# sensor.net
KiCad netlist of a schematic drawn in EAGLE
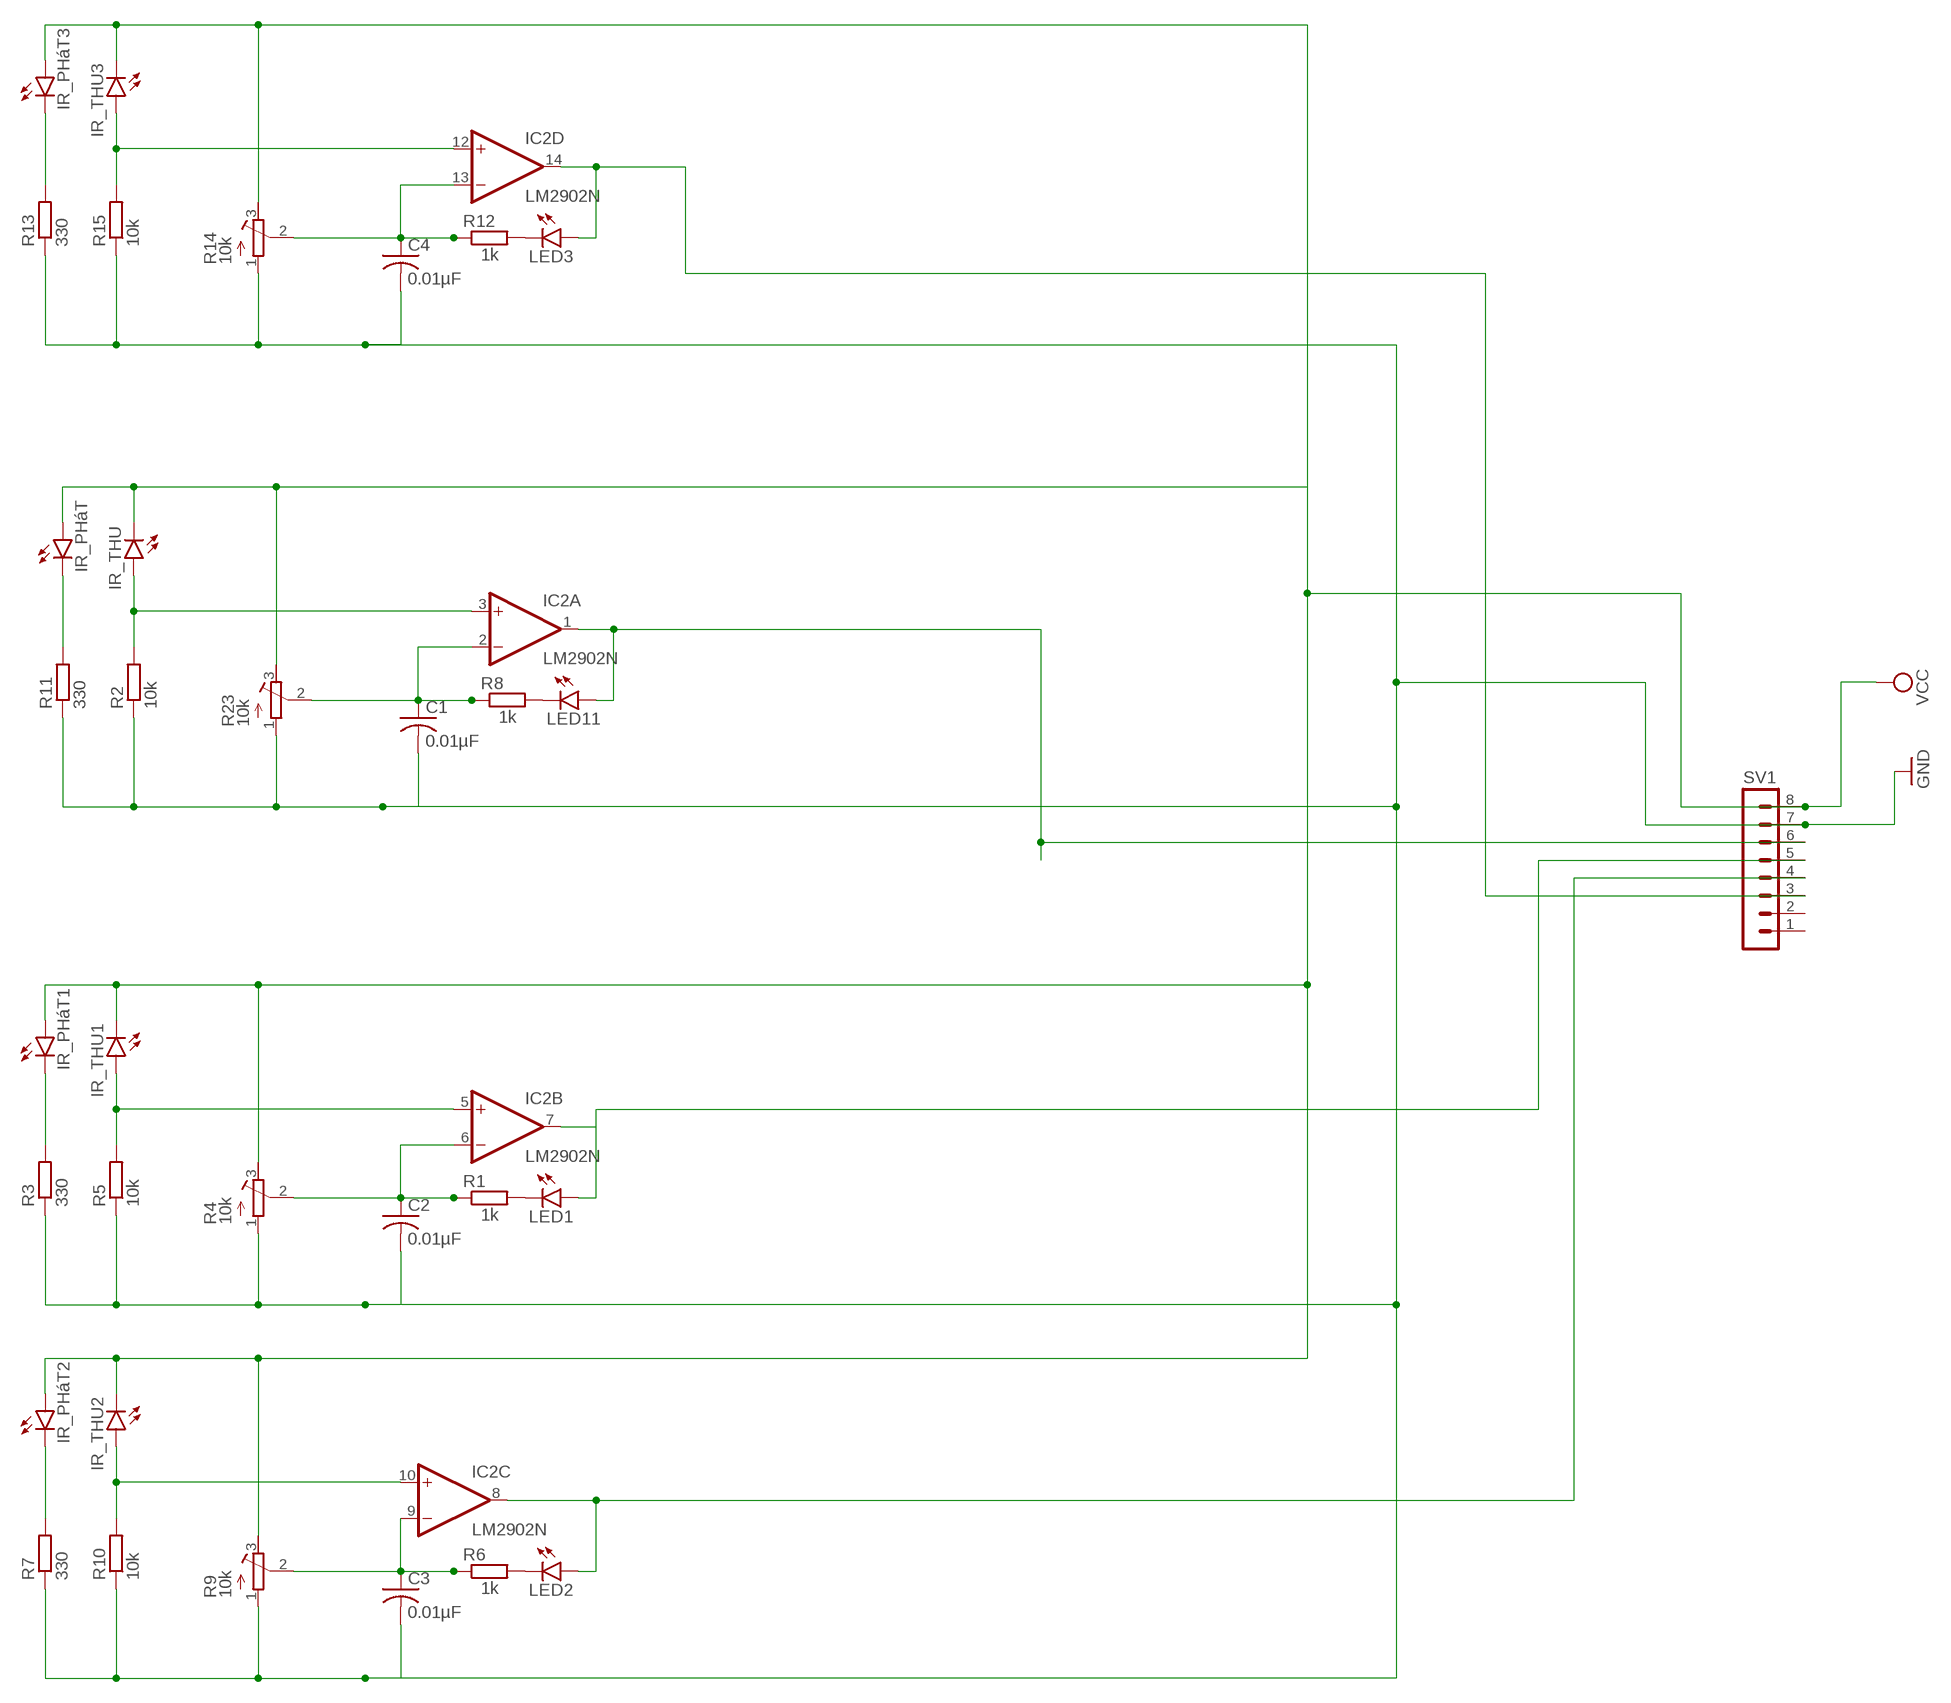
[diagram p0: schematic, sheet 1]

(export (version "E")
  (design (tool "Eeschema 10.0.6"))
  (components
    (comp (ref "C1")
      (value "0.01µF")
      (footprint "eagle-import:C025-040X050")
      (libsource (lib "eagle-import") (part "C-US025-040X050"))
    )
    (comp (ref "C2")
      (value "0.01µF")
      (footprint "eagle-import:C025-040X050")
      (libsource (lib "eagle-import") (part "C-US025-040X050"))
    )
    (comp (ref "C3")
      (value "0.01µF")
      (footprint "eagle-import:C025-040X050")
      (libsource (lib "eagle-import") (part "C-US025-040X050"))
    )
    (comp (ref "C4")
      (value "0.01µF")
      (footprint "eagle-import:C025-040X050")
      (libsource (lib "eagle-import") (part "C-US025-040X050"))
    )
    (comp (ref "IC2")
      (value "LM2902N")
      (footprint "eagle-import:DIL14")
      (fields (field (name "SPICEPREFIX") "J"))
      (libsource (lib "eagle-import") (part "LM2902N"))
    )
    (comp (ref "IR_PHáT")
      (value "LED5MM")
      (footprint "eagle-import:LED5MM")
      (libsource (lib "eagle-import") (part "LED5MM"))
    )
    (comp (ref "IR_PHáT1")
      (value "LED5MM")
      (footprint "eagle-import:LED5MM")
      (libsource (lib "eagle-import") (part "LED5MM"))
    )
    (comp (ref "IR_PHáT2")
      (value "LED5MM")
      (footprint "eagle-import:LED5MM")
      (libsource (lib "eagle-import") (part "LED5MM"))
    )
    (comp (ref "IR_PHáT3")
      (value "LED5MM")
      (footprint "eagle-import:LED5MM")
      (libsource (lib "eagle-import") (part "LED5MM"))
    )
    (comp (ref "IR_THU")
      (value "LED5MM")
      (footprint "eagle-import:LED5MM")
      (libsource (lib "eagle-import") (part "LED5MM"))
    )
    (comp (ref "IR_THU1")
      (value "LED5MM")
      (footprint "eagle-import:LED5MM")
      (libsource (lib "eagle-import") (part "LED5MM"))
    )
    (comp (ref "IR_THU2")
      (value "LED5MM")
      (footprint "eagle-import:LED5MM")
      (libsource (lib "eagle-import") (part "LED5MM"))
    )
    (comp (ref "IR_THU3")
      (value "LED5MM")
      (footprint "eagle-import:LED5MM")
      (libsource (lib "eagle-import") (part "LED5MM"))
    )
    (comp (ref "LED1")
      (value "LED5MM")
      (footprint "eagle-import:LED5MM")
      (libsource (lib "eagle-import") (part "LED5MM"))
    )
    (comp (ref "LED2")
      (value "LED5MM")
      (footprint "eagle-import:LED5MM")
      (libsource (lib "eagle-import") (part "LED5MM"))
    )
    (comp (ref "LED3")
      (value "LED5MM")
      (footprint "eagle-import:LED5MM")
      (libsource (lib "eagle-import") (part "LED5MM"))
    )
    (comp (ref "LED11")
      (value "LED5MM")
      (footprint "eagle-import:LED5MM")
      (libsource (lib "eagle-import") (part "LED5MM"))
    )
    (comp (ref "R1")
      (value "1k")
      (footprint "eagle-import:0204_7")
      (libsource (lib "eagle-import") (part "R-EU_0204/7"))
    )
    (comp (ref "R2")
      (value "10k")
      (footprint "eagle-import:0204_7")
      (libsource (lib "eagle-import") (part "R-EU_0204/7"))
    )
    (comp (ref "R3")
      (value "330")
      (footprint "eagle-import:0204_7")
      (libsource (lib "eagle-import") (part "R-EU_0204/7"))
    )
    (comp (ref "R4")
      (value "10k")
      (footprint "eagle-import:RTRIM3103")
      (libsource (lib "eagle-import") (part "R-TRIMM3103"))
    )
    (comp (ref "R5")
      (value "10k")
      (footprint "eagle-import:0204_7")
      (libsource (lib "eagle-import") (part "R-EU_0204/7"))
    )
    (comp (ref "R6")
      (value "1k")
      (footprint "eagle-import:0204_7")
      (libsource (lib "eagle-import") (part "R-EU_0204/7"))
    )
    (comp (ref "R7")
      (value "330")
      (footprint "eagle-import:0204_7")
      (libsource (lib "eagle-import") (part "R-EU_0204/7"))
    )
    (comp (ref "R8")
      (value "1k")
      (footprint "eagle-import:0204_7")
      (libsource (lib "eagle-import") (part "R-EU_0204/7"))
    )
    (comp (ref "R9")
      (value "10k")
      (footprint "eagle-import:RTRIM3103")
      (libsource (lib "eagle-import") (part "R-TRIMM3103"))
    )
    (comp (ref "R10")
      (value "10k")
      (footprint "eagle-import:0204_7")
      (libsource (lib "eagle-import") (part "R-EU_0204/7"))
    )
    (comp (ref "R11")
      (value "330")
      (footprint "eagle-import:0204_7")
      (libsource (lib "eagle-import") (part "R-EU_0204/7"))
    )
    (comp (ref "R12")
      (value "1k")
      (footprint "eagle-import:0204_7")
      (libsource (lib "eagle-import") (part "R-EU_0204/7"))
    )
    (comp (ref "R13")
      (value "330")
      (footprint "eagle-import:0204_7")
      (libsource (lib "eagle-import") (part "R-EU_0204/7"))
    )
    (comp (ref "R14")
      (value "10k")
      (footprint "eagle-import:RTRIM3103")
      (libsource (lib "eagle-import") (part "R-TRIMM3103"))
    )
    (comp (ref "R15")
      (value "10k")
      (footprint "eagle-import:0204_7")
      (libsource (lib "eagle-import") (part "R-EU_0204/7"))
    )
    (comp (ref "R23")
      (value "10k")
      (footprint "eagle-import:RTRIM3103")
      (libsource (lib "eagle-import") (part "R-TRIMM3103"))
    )
    (comp (ref "SV1")
      (value "MA08-1W")
      (footprint "eagle-import:MA08-1W")
      (libsource (lib "eagle-import") (part "MA08-1W"))
    )
  )
  (nets
    (net (code "1") (name "GND") (class "Default")
      (node (ref "C1") (pin "2") (pinfunction "2_2") (pintype "passive"))
      (node (ref "C2") (pin "2") (pinfunction "2_2") (pintype "passive"))
      (node (ref "C3") (pin "2") (pinfunction "2_2") (pintype "passive"))
      (node (ref "C4") (pin "2") (pinfunction "2_2") (pintype "passive"))
      (node (ref "R10") (pin "1") (pinfunction "1_1") (pintype "passive"))
      (node (ref "R11") (pin "1") (pinfunction "1_1") (pintype "passive"))
      (node (ref "R13") (pin "1") (pinfunction "1_1") (pintype "passive"))
      (node (ref "R14") (pin "1") (pinfunction "A_1") (pintype "passive"))
      (node (ref "R15") (pin "1") (pinfunction "1_1") (pintype "passive"))
      (node (ref "R2") (pin "1") (pinfunction "1_1") (pintype "passive"))
      (node (ref "R23") (pin "1") (pinfunction "A_1") (pintype "passive"))
      (node (ref "R3") (pin "1") (pinfunction "1_1") (pintype "passive"))
      (node (ref "R4") (pin "1") (pinfunction "A_1") (pintype "passive"))
      (node (ref "R5") (pin "1") (pinfunction "1_1") (pintype "passive"))
      (node (ref "R7") (pin "1") (pinfunction "1_1") (pintype "passive"))
      (node (ref "R9") (pin "1") (pinfunction "A_1") (pintype "passive"))
      (node (ref "SV1") (pin "7") (pinfunction "7_7") (pintype "passive"))
    )
    (net (code "2") (name "Net-(IC2A-+IN)") (class "Default")
      (node (ref "IC2") (pin "3") (pinfunction "+IN_3") (pintype "input"))
      (node (ref "IR_THU") (pin "A") (pinfunction "A_A") (pintype "passive"))
      (node (ref "R2") (pin "2") (pinfunction "2_2") (pintype "passive"))
    )
    (net (code "3") (name "Net-(IC2A--IN)") (class "Default")
      (node (ref "C1") (pin "1") (pinfunction "1_1") (pintype "passive"))
      (node (ref "IC2") (pin "2") (pinfunction "-IN_2") (pintype "input"))
      (node (ref "R23") (pin "2") (pinfunction "S_2") (pintype "passive"))
      (node (ref "R8") (pin "1") (pinfunction "1_1") (pintype "passive"))
    )
    (net (code "4") (name "Net-(IC2A-OUT)") (class "Default")
      (node (ref "IC2") (pin "1") (pinfunction "OUT_1") (pintype "output"))
      (node (ref "LED11") (pin "A") (pinfunction "A_A") (pintype "passive"))
      (node (ref "SV1") (pin "6") (pinfunction "6_6") (pintype "passive"))
    )
    (net (code "5") (name "Net-(IC2B-+IN)") (class "Default")
      (node (ref "IC2") (pin "5") (pinfunction "+IN_5") (pintype "input"))
      (node (ref "IR_THU1") (pin "A") (pinfunction "A_A") (pintype "passive"))
      (node (ref "R5") (pin "2") (pinfunction "2_2") (pintype "passive"))
    )
    (net (code "6") (name "Net-(IC2B--IN)") (class "Default")
      (node (ref "C2") (pin "1") (pinfunction "1_1") (pintype "passive"))
      (node (ref "IC2") (pin "6") (pinfunction "-IN_6") (pintype "input"))
      (node (ref "R1") (pin "1") (pinfunction "1_1") (pintype "passive"))
      (node (ref "R4") (pin "2") (pinfunction "S_2") (pintype "passive"))
    )
    (net (code "7") (name "Net-(IC2B-OUT)") (class "Default")
      (node (ref "IC2") (pin "7") (pinfunction "OUT_7") (pintype "output"))
      (node (ref "LED1") (pin "A") (pinfunction "A_A") (pintype "passive"))
      (node (ref "SV1") (pin "5") (pinfunction "5_5") (pintype "passive"))
    )
    (net (code "8") (name "Net-(IC2C-+IN)") (class "Default")
      (node (ref "IC2") (pin "10") (pinfunction "+IN_10") (pintype "input"))
      (node (ref "IR_THU2") (pin "A") (pinfunction "A_A") (pintype "passive"))
      (node (ref "R10") (pin "2") (pinfunction "2_2") (pintype "passive"))
    )
    (net (code "9") (name "Net-(IC2C--IN)") (class "Default")
      (node (ref "C3") (pin "1") (pinfunction "1_1") (pintype "passive"))
      (node (ref "IC2") (pin "9") (pinfunction "-IN_9") (pintype "input"))
      (node (ref "R6") (pin "1") (pinfunction "1_1") (pintype "passive"))
      (node (ref "R9") (pin "2") (pinfunction "S_2") (pintype "passive"))
    )
    (net (code "10") (name "Net-(IC2C-OUT)") (class "Default")
      (node (ref "IC2") (pin "8") (pinfunction "OUT_8") (pintype "output"))
      (node (ref "LED2") (pin "A") (pinfunction "A_A") (pintype "passive"))
      (node (ref "SV1") (pin "4") (pinfunction "4_4") (pintype "passive"))
    )
    (net (code "11") (name "Net-(IC2D-+IN)") (class "Default")
      (node (ref "IC2") (pin "12") (pinfunction "+IN_12") (pintype "input"))
      (node (ref "IR_THU3") (pin "A") (pinfunction "A_A") (pintype "passive"))
      (node (ref "R15") (pin "2") (pinfunction "2_2") (pintype "passive"))
    )
    (net (code "12") (name "Net-(IC2D--IN)") (class "Default")
      (node (ref "C4") (pin "1") (pinfunction "1_1") (pintype "passive"))
      (node (ref "IC2") (pin "13") (pinfunction "-IN_13") (pintype "input"))
      (node (ref "R12") (pin "1") (pinfunction "1_1") (pintype "passive"))
      (node (ref "R14") (pin "2") (pinfunction "S_2") (pintype "passive"))
    )
    (net (code "13") (name "Net-(IC2D-OUT)") (class "Default")
      (node (ref "IC2") (pin "14") (pinfunction "OUT_14") (pintype "output"))
      (node (ref "LED3") (pin "A") (pinfunction "A_A") (pintype "passive"))
      (node (ref "SV1") (pin "3") (pinfunction "3_3") (pintype "passive"))
    )
    (net (code "14") (name "Net-(IR_PHáT-C)") (class "Default")
      (node (ref "IR_PHáT") (pin "K") (pinfunction "C_K") (pintype "passive"))
      (node (ref "R11") (pin "2") (pinfunction "2_2") (pintype "passive"))
    )
    (net (code "15") (name "Net-(IR_PHáT1-C)") (class "Default")
      (node (ref "IR_PHáT1") (pin "K") (pinfunction "C_K") (pintype "passive"))
      (node (ref "R3") (pin "2") (pinfunction "2_2") (pintype "passive"))
    )
    (net (code "16") (name "Net-(IR_PHáT2-C)") (class "Default")
      (node (ref "IR_PHáT2") (pin "K") (pinfunction "C_K") (pintype "passive"))
      (node (ref "R7") (pin "2") (pinfunction "2_2") (pintype "passive"))
    )
    (net (code "17") (name "Net-(IR_PHáT3-C)") (class "Default")
      (node (ref "IR_PHáT3") (pin "K") (pinfunction "C_K") (pintype "passive"))
      (node (ref "R13") (pin "2") (pinfunction "2_2") (pintype "passive"))
    )
    (net (code "18") (name "Net-(LED1-C)") (class "Default")
      (node (ref "LED1") (pin "K") (pinfunction "C_K") (pintype "passive"))
      (node (ref "R1") (pin "2") (pinfunction "2_2") (pintype "passive"))
    )
    (net (code "19") (name "Net-(LED2-C)") (class "Default")
      (node (ref "LED2") (pin "K") (pinfunction "C_K") (pintype "passive"))
      (node (ref "R6") (pin "2") (pinfunction "2_2") (pintype "passive"))
    )
    (net (code "20") (name "Net-(LED3-C)") (class "Default")
      (node (ref "LED3") (pin "K") (pinfunction "C_K") (pintype "passive"))
      (node (ref "R12") (pin "2") (pinfunction "2_2") (pintype "passive"))
    )
    (net (code "21") (name "Net-(LED11-C)") (class "Default")
      (node (ref "LED11") (pin "K") (pinfunction "C_K") (pintype "passive"))
      (node (ref "R8") (pin "2") (pinfunction "2_2") (pintype "passive"))
    )
    (net (code "22") (name "VCC") (class "Default")
      (node (ref "IR_PHáT") (pin "A") (pinfunction "A_A") (pintype "passive"))
      (node (ref "IR_PHáT1") (pin "A") (pinfunction "A_A") (pintype "passive"))
      (node (ref "IR_PHáT2") (pin "A") (pinfunction "A_A") (pintype "passive"))
      (node (ref "IR_PHáT3") (pin "A") (pinfunction "A_A") (pintype "passive"))
      (node (ref "IR_THU") (pin "K") (pinfunction "C_K") (pintype "passive"))
      (node (ref "IR_THU1") (pin "K") (pinfunction "C_K") (pintype "passive"))
      (node (ref "IR_THU2") (pin "K") (pinfunction "C_K") (pintype "passive"))
      (node (ref "IR_THU3") (pin "K") (pinfunction "C_K") (pintype "passive"))
      (node (ref "R14") (pin "3") (pinfunction "E_3") (pintype "passive"))
      (node (ref "R23") (pin "3") (pinfunction "E_3") (pintype "passive"))
      (node (ref "R4") (pin "3") (pinfunction "E_3") (pintype "passive"))
      (node (ref "R9") (pin "3") (pinfunction "E_3") (pintype "passive"))
      (node (ref "SV1") (pin "8") (pinfunction "8_8") (pintype "passive"))
    )
    (net (code "23") (name "unconnected-(SV1-Pad1)") (class "Default")
      (node (ref "SV1") (pin "1") (pinfunction "1_1") (pintype "passive"))
    )
    (net (code "24") (name "unconnected-(SV1-Pad2)") (class "Default")
      (node (ref "SV1") (pin "2") (pinfunction "2_2") (pintype "passive"))
    )
  )
)
